# 07_Ethernet_Interface.net
KiCad netlist of a schematic drawn in Altium Designer
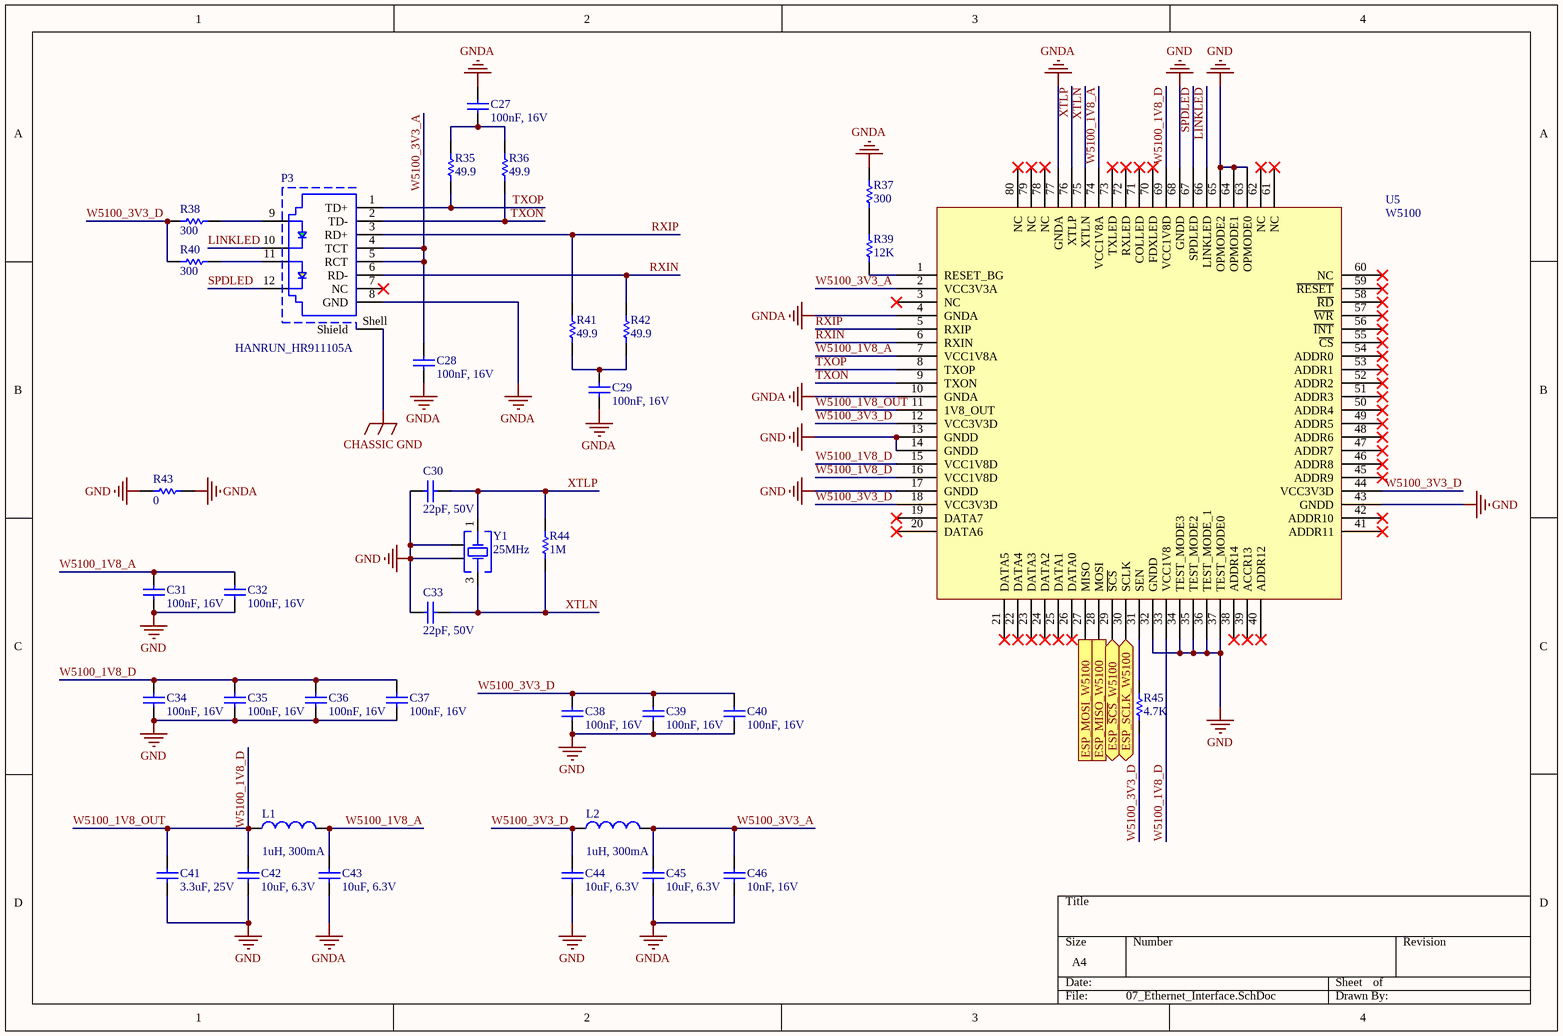
[diagram p0: 07_Ethernet_Interface.SchDoc]

(export (version "E")
  (design (tool "Eeschema 10.0.6"))
  (components
    (comp (ref "C27")
      (value "100nF, 16V")
      (footprint "WCAP-CSGP_0603_H=0.8mm_Reflow")
      (description "WCAP-CSGP Multilayer Ceramic Chip Capacitor, General Purpose, size 0603, X7R, 100nF, 16V")
      (fields
        (field (name "MANUFACTURER PART NUMBER") "885012206046")
        (field (name "MANUFACTURER") "Wurth Elektronik")
      )
      (libsource (lib "Altium_WCAP-CSGP (rev20a)") (part "885012206046"))
    )
    (comp (ref "C28")
      (value "100nF, 16V")
      (footprint "WCAP-CSGP_0603_H=0.8mm_Reflow")
      (description "WCAP-CSGP Multilayer Ceramic Chip Capacitor, General Purpose, size 0603, X7R, 100nF, 16V")
      (fields
        (field (name "MANUFACTURER PART NUMBER") "885012206046")
        (field (name "MANUFACTURER") "Wurth Elektronik")
      )
      (libsource (lib "Altium_WCAP-CSGP (rev20a)") (part "885012206046"))
    )
    (comp (ref "C29")
      (value "100nF, 16V")
      (footprint "WCAP-CSGP_0603_H=0.8mm_Reflow")
      (description "WCAP-CSGP Multilayer Ceramic Chip Capacitor, General Purpose, size 0603, X7R, 100nF, 16V")
      (fields
        (field (name "MANUFACTURER PART NUMBER") "885012206046")
        (field (name "MANUFACTURER") "Wurth Elektronik")
      )
      (libsource (lib "Altium_WCAP-CSGP (rev20a)") (part "885012206046"))
    )
    (comp (ref "C30")
      (value "22pF, 50V")
      (footprint "WCAP-CSGP_0603_H=0.8mm_Reflow")
      (description "WCAP-CSGP Multilayer Ceramic Chip Capacitor, General Purpose, size 0603, NP0, 22pF, 50V")
      (fields
        (field (name "MANUFACTURER PART NUMBER") "885012006053")
        (field (name "MANUFACTURER") "Wurth Elektronik")
      )
      (libsource (lib "Altium_WCAP-CSGP (rev20a)") (part "885012006053"))
    )
    (comp (ref "C31")
      (value "100nF, 16V")
      (footprint "WCAP-CSGP_0603_H=0.8mm_Reflow")
      (description "WCAP-CSGP Multilayer Ceramic Chip Capacitor, General Purpose, size 0603, X7R, 100nF, 16V")
      (fields
        (field (name "MANUFACTURER PART NUMBER") "885012206046")
        (field (name "MANUFACTURER") "Wurth Elektronik")
      )
      (libsource (lib "Altium_WCAP-CSGP (rev20a)") (part "885012206046"))
    )
    (comp (ref "C32")
      (value "100nF, 16V")
      (footprint "WCAP-CSGP_0603_H=0.8mm_Reflow")
      (description "WCAP-CSGP Multilayer Ceramic Chip Capacitor, General Purpose, size 0603, X7R, 100nF, 16V")
      (fields
        (field (name "MANUFACTURER PART NUMBER") "885012206046")
        (field (name "MANUFACTURER") "Wurth Elektronik")
      )
      (libsource (lib "Altium_WCAP-CSGP (rev20a)") (part "885012206046"))
    )
    (comp (ref "C33")
      (value "22pF, 50V")
      (footprint "WCAP-CSGP_0603_H=0.8mm_Reflow")
      (description "WCAP-CSGP Multilayer Ceramic Chip Capacitor, General Purpose, size 0603, NP0, 22pF, 50V")
      (fields
        (field (name "MANUFACTURER PART NUMBER") "885012006053")
        (field (name "MANUFACTURER") "Wurth Elektronik")
      )
      (libsource (lib "Altium_WCAP-CSGP (rev20a)") (part "885012006053"))
    )
    (comp (ref "C34")
      (value "100nF, 16V")
      (footprint "WCAP-CSGP_0603_H=0.8mm_Reflow")
      (description "WCAP-CSGP Multilayer Ceramic Chip Capacitor, General Purpose, size 0603, X7R, 100nF, 16V")
      (fields
        (field (name "MANUFACTURER PART NUMBER") "885012206046")
        (field (name "MANUFACTURER") "Wurth Elektronik")
      )
      (libsource (lib "Altium_WCAP-CSGP (rev20a)") (part "885012206046"))
    )
    (comp (ref "C35")
      (value "100nF, 16V")
      (footprint "WCAP-CSGP_0603_H=0.8mm_Reflow")
      (description "WCAP-CSGP Multilayer Ceramic Chip Capacitor, General Purpose, size 0603, X7R, 100nF, 16V")
      (fields
        (field (name "MANUFACTURER PART NUMBER") "885012206046")
        (field (name "MANUFACTURER") "Wurth Elektronik")
      )
      (libsource (lib "Altium_WCAP-CSGP (rev20a)") (part "885012206046"))
    )
    (comp (ref "C36")
      (value "100nF, 16V")
      (footprint "WCAP-CSGP_0603_H=0.8mm_Reflow")
      (description "WCAP-CSGP Multilayer Ceramic Chip Capacitor, General Purpose, size 0603, X7R, 100nF, 16V")
      (fields
        (field (name "MANUFACTURER PART NUMBER") "885012206046")
        (field (name "MANUFACTURER") "Wurth Elektronik")
      )
      (libsource (lib "Altium_WCAP-CSGP (rev20a)") (part "885012206046"))
    )
    (comp (ref "C37")
      (value "100nF, 16V")
      (footprint "WCAP-CSGP_0603_H=0.8mm_Reflow")
      (description "WCAP-CSGP Multilayer Ceramic Chip Capacitor, General Purpose, size 0603, X7R, 100nF, 16V")
      (fields
        (field (name "MANUFACTURER PART NUMBER") "885012206046")
        (field (name "MANUFACTURER") "Wurth Elektronik")
      )
      (libsource (lib "Altium_WCAP-CSGP (rev20a)") (part "885012206046"))
    )
    (comp (ref "C38")
      (value "100nF, 16V")
      (footprint "WCAP-CSGP_0603_H=0.8mm_Reflow")
      (description "WCAP-CSGP Multilayer Ceramic Chip Capacitor, General Purpose, size 0603, X7R, 100nF, 16V")
      (fields
        (field (name "MANUFACTURER PART NUMBER") "885012206046")
        (field (name "MANUFACTURER") "Wurth Elektronik")
      )
      (libsource (lib "Altium_WCAP-CSGP (rev20a)") (part "885012206046"))
    )
    (comp (ref "C39")
      (value "100nF, 16V")
      (footprint "WCAP-CSGP_0603_H=0.8mm_Reflow")
      (description "WCAP-CSGP Multilayer Ceramic Chip Capacitor, General Purpose, size 0603, X7R, 100nF, 16V")
      (fields
        (field (name "MANUFACTURER PART NUMBER") "885012206046")
        (field (name "MANUFACTURER") "Wurth Elektronik")
      )
      (libsource (lib "Altium_WCAP-CSGP (rev20a)") (part "885012206046"))
    )
    (comp (ref "C40")
      (value "100nF, 16V")
      (footprint "WCAP-CSGP_0603_H=0.8mm_Reflow")
      (description "WCAP-CSGP Multilayer Ceramic Chip Capacitor, General Purpose, size 0603, X7R, 100nF, 16V")
      (fields
        (field (name "MANUFACTURER PART NUMBER") "885012206046")
        (field (name "MANUFACTURER") "Wurth Elektronik")
      )
      (libsource (lib "Altium_WCAP-CSGP (rev20a)") (part "885012206046"))
    )
    (comp (ref "C41")
      (value "3.3uF, 25V")
      (footprint "WCAP-CSGP_0805_H=1.25mm")
      (description "WCAP-CSGP Multilayer Ceramic Chip Capacitor, General Purpose, size 0805, X5R, 3.3uF, 25V")
      (fields
        (field (name "MANUFACTURER PART NUMBER") "885012107017")
        (field (name "MANUFACTURER") "Wurth Elektronik")
      )
      (libsource (lib "Altium_WCAP-CSGP (rev20a)") (part "885012107017"))
    )
    (comp (ref "C42")
      (value "10uF, 6.3V")
      (footprint "WCAP-CSGP_0603_H=0.8mm_Reflow")
      (description "WCAP-CSGP Multilayer Ceramic Chip Capacitor, General Purpose, size 0603, X5R, 10uF, 6.3V")
      (fields
        (field (name "MANUFACTURER PART NUMBER") "885012106006")
        (field (name "MANUFACTURER") "Wurth Elektronik")
      )
      (libsource (lib "Altium_WCAP-CSGP (rev20a)") (part "885012106006"))
    )
    (comp (ref "C43")
      (value "10uF, 6.3V")
      (footprint "WCAP-CSGP_0603_H=0.8mm_Reflow")
      (description "WCAP-CSGP Multilayer Ceramic Chip Capacitor, General Purpose, size 0603, X5R, 10uF, 6.3V")
      (fields
        (field (name "MANUFACTURER PART NUMBER") "885012106006")
        (field (name "MANUFACTURER") "Wurth Elektronik")
      )
      (libsource (lib "Altium_WCAP-CSGP (rev20a)") (part "885012106006"))
    )
    (comp (ref "C44")
      (value "10uF, 6.3V")
      (footprint "WCAP-CSGP_0603_H=0.8mm_Reflow")
      (description "WCAP-CSGP Multilayer Ceramic Chip Capacitor, General Purpose, size 0603, X5R, 10uF, 6.3V")
      (fields
        (field (name "MANUFACTURER PART NUMBER") "885012106006")
        (field (name "MANUFACTURER") "Wurth Elektronik")
      )
      (libsource (lib "Altium_WCAP-CSGP (rev20a)") (part "885012106006"))
    )
    (comp (ref "C45")
      (value "10uF, 6.3V")
      (footprint "WCAP-CSGP_0603_H=0.8mm_Reflow")
      (description "WCAP-CSGP Multilayer Ceramic Chip Capacitor, General Purpose, size 0603, X5R, 10uF, 6.3V")
      (fields
        (field (name "MANUFACTURER PART NUMBER") "885012106006")
        (field (name "MANUFACTURER") "Wurth Elektronik")
      )
      (libsource (lib "Altium_WCAP-CSGP (rev20a)") (part "885012106006"))
    )
    (comp (ref "C46")
      (value "10nF, 16V")
      (footprint "WCAP-CSGP_0603_H=0.8mm_Reflow")
      (description "WCAP-CSGP Multilayer Ceramic Chip Capacitor, General Purpose, size 0603, X7R, 10nF, 16V")
      (fields
        (field (name "MANUFACTURER PART NUMBER") "885012206040")
        (field (name "MANUFACTURER") "Wurth Elektronik")
      )
      (libsource (lib "Altium_WCAP-CSGP (rev20a)") (part "885012206040"))
    )
    (comp (ref "L1")
      (value "1uH, 300mA")
      (footprint "I0603")
      (fields (field (name "Comment") "Inductor"))
      (libsource (lib "MiclsLib") (part "Inductor"))
    )
    (comp (ref "L2")
      (value "1uH, 300mA")
      (footprint "I0603")
      (fields (field (name "Comment") "Inductor"))
      (libsource (lib "MiclsLib") (part "Inductor"))
    )
    (comp (ref "P3")
      (value "HANRUN_HR911105A")
      (footprint "HANRUN_HR911105A")
      (libsource (lib "MiclsLib") (part "HANRUN_HR911105A"))
    )
    (comp (ref "R35")
      (value "49.9")
      (footprint "R0603")
      (fields (field (name "Comment") "Resistor"))
      (libsource (lib "MiclsLib") (part "Resistor"))
    )
    (comp (ref "R36")
      (value "49.9")
      (footprint "R0603")
      (fields (field (name "Comment") "Resistor"))
      (libsource (lib "MiclsLib") (part "Resistor"))
    )
    (comp (ref "R37")
      (value "300")
      (footprint "R0603")
      (fields (field (name "Comment") "Resistor"))
      (libsource (lib "MiclsLib") (part "Resistor"))
    )
    (comp (ref "R38")
      (value "300")
      (footprint "R0603")
      (fields (field (name "Comment") "Resistor"))
      (libsource (lib "MiclsLib") (part "Resistor"))
    )
    (comp (ref "R39")
      (value "12K")
      (footprint "R0603")
      (fields (field (name "Comment") "Resistor"))
      (libsource (lib "MiclsLib") (part "Resistor"))
    )
    (comp (ref "R40")
      (value "300")
      (footprint "R0603")
      (fields (field (name "Comment") "Resistor"))
      (libsource (lib "MiclsLib") (part "Resistor"))
    )
    (comp (ref "R41")
      (value "49.9")
      (footprint "R0603")
      (fields (field (name "Comment") "Resistor"))
      (libsource (lib "MiclsLib") (part "Resistor"))
    )
    (comp (ref "R42")
      (value "49.9")
      (footprint "R0603")
      (fields (field (name "Comment") "Resistor"))
      (libsource (lib "MiclsLib") (part "Resistor"))
    )
    (comp (ref "R43")
      (value "0")
      (footprint "R0603")
      (fields (field (name "Comment") "Resistor"))
      (libsource (lib "MiclsLib") (part "Resistor"))
    )
    (comp (ref "R44")
      (value "1M")
      (footprint "R0603")
      (fields (field (name "Comment") "Resistor"))
      (libsource (lib "MiclsLib") (part "Resistor"))
    )
    (comp (ref "R45")
      (value "4.7K")
      (footprint "R0603")
      (fields (field (name "Comment") "Resistor"))
      (libsource (lib "MiclsLib") (part "Resistor"))
    )
    (comp (ref "U5")
      (value "W5100")
      (footprint "CQFP40P1200X1200X160-80N")
      (libsource (lib "MiclsLib") (part "W5100"))
    )
    (comp (ref "Y1")
      (value "25MHz")
      (footprint "WE-XTAL_CFPX-180")
      (description "WE-XTAL Quartz Crystal, SMT, CFPX-180, 25MHz, +/-20ppm")
      (fields
        (field (name "MANUFACTURER PART NUMBER") "830108340809")
        (field (name "MANUFACTURER") "Wurth Elektronik")
      )
      (libsource (lib "Altium_WE-XTAL (rev20c)") (part "830108340809"))
    )
  )
  (nets
    (net (code "1") (name "/ESP_MISO_W5100") (class "Default")
      (node (ref "U5") (pin "28") (pinfunction "MOSI_28") (pintype "passive"))
    )
    (net (code "2") (name "/ESP_MOSI_W5100") (class "Default")
      (node (ref "U5") (pin "27") (pinfunction "MISO_27") (pintype "passive"))
    )
    (net (code "3") (name "/ESP_SCLK_W5100") (class "Default")
      (node (ref "U5") (pin "30") (pinfunction "SCLK_30") (pintype "passive"))
    )
    (net (code "4") (name "/ESP_~{SCS}_W5100") (class "Default")
      (node (ref "U5") (pin "29") (pinfunction "~{SCS}_29") (pintype "passive"))
    )
    (net (code "5") (name "/LINKLED") (class "Default")
      (node (ref "P3") (pin "10") (pinfunction "10_10") (pintype "passive"))
      (node (ref "U5") (pin "66") (pinfunction "LINKLED_66") (pintype "passive"))
    )
    (net (code "6") (name "/RXIN") (class "Default")
      (node (ref "P3") (pin "6") (pinfunction "RD-_6") (pintype "passive"))
      (node (ref "R42") (pin "1") (pinfunction "1_1") (pintype "passive"))
      (node (ref "U5") (pin "6") (pinfunction "RXIN_6") (pintype "passive"))
    )
    (net (code "7") (name "/RXIP") (class "Default")
      (node (ref "P3") (pin "3") (pinfunction "RD+_3") (pintype "passive"))
      (node (ref "R41") (pin "1") (pinfunction "1_1") (pintype "passive"))
      (node (ref "U5") (pin "5") (pinfunction "RXIP_5") (pintype "passive"))
    )
    (net (code "8") (name "/SPDLED") (class "Default")
      (node (ref "P3") (pin "12") (pinfunction "12_12") (pintype "passive"))
      (node (ref "U5") (pin "67") (pinfunction "SPDLED_67") (pintype "passive"))
    )
    (net (code "9") (name "/TXON") (class "Default")
      (node (ref "P3") (pin "2") (pinfunction "TD-_2") (pintype "passive"))
      (node (ref "R36") (pin "1") (pinfunction "1_1") (pintype "passive"))
      (node (ref "U5") (pin "9") (pinfunction "TXON_9") (pintype "passive"))
    )
    (net (code "10") (name "/TXOP") (class "Default")
      (node (ref "P3") (pin "1") (pinfunction "TD+_1") (pintype "passive"))
      (node (ref "R35") (pin "1") (pinfunction "1_1") (pintype "passive"))
      (node (ref "U5") (pin "8") (pinfunction "TXOP_8") (pintype "passive"))
    )
    (net (code "11") (name "/W5100_1V8_A") (class "Default")
      (node (ref "C31") (pin "2") (pinfunction "2_2") (pintype "passive"))
      (node (ref "C32") (pin "2") (pinfunction "2_2") (pintype "passive"))
      (node (ref "C43") (pin "2") (pinfunction "2_2") (pintype "passive"))
      (node (ref "L1") (pin "2") (pinfunction "2_2") (pintype "passive"))
      (node (ref "U5") (pin "7") (pinfunction "VCC1V8A_7") (pintype "passive"))
      (node (ref "U5") (pin "74") (pinfunction "VCC1V8A_74") (pintype "passive"))
    )
    (net (code "12") (name "/W5100_1V8_D") (class "Default")
      (node (ref "C34") (pin "2") (pinfunction "2_2") (pintype "passive"))
      (node (ref "C35") (pin "2") (pinfunction "2_2") (pintype "passive"))
      (node (ref "C36") (pin "2") (pinfunction "2_2") (pintype "passive"))
      (node (ref "C37") (pin "2") (pinfunction "2_2") (pintype "passive"))
      (node (ref "C41") (pin "2") (pinfunction "2_2") (pintype "passive"))
      (node (ref "C42") (pin "2") (pinfunction "2_2") (pintype "passive"))
      (node (ref "L1") (pin "1") (pinfunction "1_1") (pintype "passive"))
      (node (ref "U5") (pin "11") (pinfunction "1V8_OUT_11") (pintype "passive"))
      (node (ref "U5") (pin "15") (pinfunction "VCC1V8D_15") (pintype "passive"))
      (node (ref "U5") (pin "16") (pinfunction "VCC1V8D_16") (pintype "passive"))
      (node (ref "U5") (pin "33") (pinfunction "VCC1V8_33") (pintype "passive"))
      (node (ref "U5") (pin "69") (pinfunction "VCC1V8D_69") (pintype "passive"))
    )
    (net (code "13") (name "/W5100_3V3_A") (class "Default")
      (node (ref "C28") (pin "2") (pinfunction "2_2") (pintype "passive"))
      (node (ref "C45") (pin "2") (pinfunction "2_2") (pintype "passive"))
      (node (ref "C46") (pin "2") (pinfunction "2_2") (pintype "passive"))
      (node (ref "L2") (pin "2") (pinfunction "2_2") (pintype "passive"))
      (node (ref "P3") (pin "4") (pinfunction "TCT_4") (pintype "passive"))
      (node (ref "P3") (pin "5") (pinfunction "RCT_5") (pintype "passive"))
      (node (ref "U5") (pin "2") (pinfunction "VCC3V3A_2") (pintype "passive"))
    )
    (net (code "14") (name "/W5100_3V3_D") (class "Default")
      (node (ref "C38") (pin "2") (pinfunction "2_2") (pintype "passive"))
      (node (ref "C39") (pin "2") (pinfunction "2_2") (pintype "passive"))
      (node (ref "C40") (pin "2") (pinfunction "2_2") (pintype "passive"))
      (node (ref "C44") (pin "2") (pinfunction "2_2") (pintype "passive"))
      (node (ref "L2") (pin "1") (pinfunction "1_1") (pintype "passive"))
      (node (ref "R38") (pin "2") (pinfunction "2_2") (pintype "passive"))
      (node (ref "R40") (pin "2") (pinfunction "2_2") (pintype "passive"))
      (node (ref "R45") (pin "1") (pinfunction "1_1") (pintype "passive"))
      (node (ref "U5") (pin "12") (pinfunction "VCC3V3D_12") (pintype "passive"))
      (node (ref "U5") (pin "18") (pinfunction "VCC3V3D_18") (pintype "passive"))
      (node (ref "U5") (pin "44") (pinfunction "VCC3V3D_44") (pintype "passive"))
    )
    (net (code "15") (name "/XTLN") (class "Default")
      (node (ref "C33") (pin "2") (pinfunction "2_2") (pintype "passive"))
      (node (ref "R44") (pin "1") (pinfunction "1_1") (pintype "passive"))
      (node (ref "U5") (pin "75") (pinfunction "XTLN_75") (pintype "passive"))
      (node (ref "Y1") (pin "3") (pinfunction "Crystal_3") (pintype "passive"))
    )
    (net (code "16") (name "/XTLP") (class "Default")
      (node (ref "C30") (pin "2") (pinfunction "2_2") (pintype "passive"))
      (node (ref "R44") (pin "2") (pinfunction "2_2") (pintype "passive"))
      (node (ref "U5") (pin "76") (pinfunction "XTLP_76") (pintype "passive"))
      (node (ref "Y1") (pin "1") (pinfunction "Crystal_1") (pintype "passive"))
    )
    (net (code "17") (name "CHASSIC GND") (class "Default")
      (node (ref "P3") (pin "Shell") (pinfunction "Shield_Shell") (pintype "passive"))
    )
    (net (code "18") (name "GND") (class "Default")
      (node (ref "C30") (pin "1") (pinfunction "1_1") (pintype "passive"))
      (node (ref "C31") (pin "1") (pinfunction "1_1") (pintype "passive"))
      (node (ref "C32") (pin "1") (pinfunction "1_1") (pintype "passive"))
      (node (ref "C33") (pin "1") (pinfunction "1_1") (pintype "passive"))
      (node (ref "C34") (pin "1") (pinfunction "1_1") (pintype "passive"))
      (node (ref "C35") (pin "1") (pinfunction "1_1") (pintype "passive"))
      (node (ref "C36") (pin "1") (pinfunction "1_1") (pintype "passive"))
      (node (ref "C37") (pin "1") (pinfunction "1_1") (pintype "passive"))
      (node (ref "C38") (pin "1") (pinfunction "1_1") (pintype "passive"))
      (node (ref "C39") (pin "1") (pinfunction "1_1") (pintype "passive"))
      (node (ref "C40") (pin "1") (pinfunction "1_1") (pintype "passive"))
      (node (ref "C41") (pin "1") (pinfunction "1_1") (pintype "passive"))
      (node (ref "C42") (pin "1") (pinfunction "1_1") (pintype "passive"))
      (node (ref "C44") (pin "1") (pinfunction "1_1") (pintype "passive"))
      (node (ref "R43") (pin "2") (pinfunction "2_2") (pintype "passive"))
      (node (ref "U5") (pin "13") (pinfunction "GNDD_13") (pintype "passive"))
      (node (ref "U5") (pin "14") (pinfunction "GNDD_14") (pintype "passive"))
      (node (ref "U5") (pin "17") (pinfunction "GNDD_17") (pintype "passive"))
      (node (ref "U5") (pin "32") (pinfunction "GNDD_32") (pintype "passive"))
      (node (ref "U5") (pin "34") (pinfunction "TEST_MODE3_34") (pintype "passive"))
      (node (ref "U5") (pin "35") (pinfunction "TEST_MODE2_35") (pintype "passive"))
      (node (ref "U5") (pin "36") (pinfunction "TEST_MODE_1_36") (pintype "passive"))
      (node (ref "U5") (pin "37") (pinfunction "TEST_MODE0_37") (pintype "passive"))
      (node (ref "U5") (pin "43") (pinfunction "GNDD_43") (pintype "passive"))
      (node (ref "U5") (pin "63") (pinfunction "OPMODE0_63") (pintype "passive"))
      (node (ref "U5") (pin "64") (pinfunction "OPMODE1_64") (pintype "passive"))
      (node (ref "U5") (pin "65") (pinfunction "OPMODE2_65") (pintype "passive"))
      (node (ref "U5") (pin "68") (pinfunction "GNDD_68") (pintype "passive"))
      (node (ref "Y1") (pin "2") (pinfunction "GND&Lid_2") (pintype "passive"))
      (node (ref "Y1") (pin "4") (pinfunction "GND&Lid_4") (pintype "passive"))
    )
    (net (code "19") (name "GNDA") (class "Default")
      (node (ref "C27") (pin "2") (pinfunction "2_2") (pintype "passive"))
      (node (ref "C28") (pin "1") (pinfunction "1_1") (pintype "passive"))
      (node (ref "C29") (pin "2") (pinfunction "2_2") (pintype "passive"))
      (node (ref "C43") (pin "1") (pinfunction "1_1") (pintype "passive"))
      (node (ref "C45") (pin "1") (pinfunction "1_1") (pintype "passive"))
      (node (ref "C46") (pin "1") (pinfunction "1_1") (pintype "passive"))
      (node (ref "P3") (pin "8") (pinfunction "GND_8") (pintype "passive"))
      (node (ref "R37") (pin "2") (pinfunction "2_2") (pintype "passive"))
      (node (ref "R43") (pin "1") (pinfunction "1_1") (pintype "passive"))
      (node (ref "U5") (pin "10") (pinfunction "GNDA_10") (pintype "passive"))
      (node (ref "U5") (pin "4") (pinfunction "GNDA_4") (pintype "passive"))
      (node (ref "U5") (pin "77") (pinfunction "GNDA_77") (pintype "passive"))
    )
    (net (code "20") (name "Net-(C27-Pad1)") (class "Default")
      (node (ref "C27") (pin "1") (pinfunction "1_1") (pintype "passive"))
      (node (ref "R35") (pin "2") (pinfunction "2_2") (pintype "passive"))
      (node (ref "R36") (pin "2") (pinfunction "2_2") (pintype "passive"))
    )
    (net (code "21") (name "Net-(C29-Pad1)") (class "Default")
      (node (ref "C29") (pin "1") (pinfunction "1_1") (pintype "passive"))
      (node (ref "R41") (pin "2") (pinfunction "2_2") (pintype "passive"))
      (node (ref "R42") (pin "2") (pinfunction "2_2") (pintype "passive"))
    )
    (net (code "22") (name "Net-(P3-Pad9)") (class "Default")
      (node (ref "P3") (pin "9") (pinfunction "9_9") (pintype "passive"))
      (node (ref "R38") (pin "1") (pinfunction "1_1") (pintype "passive"))
    )
    (net (code "23") (name "Net-(P3-Pad11)") (class "Default")
      (node (ref "P3") (pin "11") (pinfunction "11_11") (pintype "passive"))
      (node (ref "R40") (pin "1") (pinfunction "1_1") (pintype "passive"))
    )
    (net (code "24") (name "Net-(R37-Pad1)") (class "Default")
      (node (ref "R37") (pin "1") (pinfunction "1_1") (pintype "passive"))
      (node (ref "R39") (pin "2") (pinfunction "2_2") (pintype "passive"))
    )
    (net (code "25") (name "Net-(U5-RESET_BG)") (class "Default")
      (node (ref "R39") (pin "1") (pinfunction "1_1") (pintype "passive"))
      (node (ref "U5") (pin "1") (pinfunction "RESET_BG_1") (pintype "passive"))
    )
    (net (code "26") (name "Net-(U5-SEN)") (class "Default")
      (node (ref "R45") (pin "2") (pinfunction "2_2") (pintype "passive"))
      (node (ref "U5") (pin "31") (pinfunction "SEN_31") (pintype "passive"))
    )
    (net (code "27") (name "unconnected-(P3-NC-Pad7)") (class "Default")
      (node (ref "P3") (pin "7") (pinfunction "NC_7") (pintype "passive+no_connect"))
    )
    (net (code "28") (name "unconnected-(U5-ACCR13-Pad39)") (class "Default")
      (node (ref "U5") (pin "39") (pinfunction "ACCR13_39") (pintype "passive+no_connect"))
    )
    (net (code "29") (name "unconnected-(U5-ADDR0-Pad54)") (class "Default")
      (node (ref "U5") (pin "54") (pinfunction "ADDR0_54") (pintype "passive+no_connect"))
    )
    (net (code "30") (name "unconnected-(U5-ADDR1-Pad53)") (class "Default")
      (node (ref "U5") (pin "53") (pinfunction "ADDR1_53") (pintype "passive+no_connect"))
    )
    (net (code "31") (name "unconnected-(U5-ADDR2-Pad52)") (class "Default")
      (node (ref "U5") (pin "52") (pinfunction "ADDR2_52") (pintype "passive+no_connect"))
    )
    (net (code "32") (name "unconnected-(U5-ADDR3-Pad51)") (class "Default")
      (node (ref "U5") (pin "51") (pinfunction "ADDR3_51") (pintype "passive+no_connect"))
    )
    (net (code "33") (name "unconnected-(U5-ADDR4-Pad50)") (class "Default")
      (node (ref "U5") (pin "50") (pinfunction "ADDR4_50") (pintype "passive+no_connect"))
    )
    (net (code "34") (name "unconnected-(U5-ADDR5-Pad49)") (class "Default")
      (node (ref "U5") (pin "49") (pinfunction "ADDR5_49") (pintype "passive+no_connect"))
    )
    (net (code "35") (name "unconnected-(U5-ADDR6-Pad48)") (class "Default")
      (node (ref "U5") (pin "48") (pinfunction "ADDR6_48") (pintype "passive+no_connect"))
    )
    (net (code "36") (name "unconnected-(U5-ADDR7-Pad47)") (class "Default")
      (node (ref "U5") (pin "47") (pinfunction "ADDR7_47") (pintype "passive+no_connect"))
    )
    (net (code "37") (name "unconnected-(U5-ADDR8-Pad46)") (class "Default")
      (node (ref "U5") (pin "46") (pinfunction "ADDR8_46") (pintype "passive+no_connect"))
    )
    (net (code "38") (name "unconnected-(U5-ADDR9-Pad45)") (class "Default")
      (node (ref "U5") (pin "45") (pinfunction "ADDR9_45") (pintype "passive+no_connect"))
    )
    (net (code "39") (name "unconnected-(U5-ADDR10-Pad42)") (class "Default")
      (node (ref "U5") (pin "42") (pinfunction "ADDR10_42") (pintype "passive+no_connect"))
    )
    (net (code "40") (name "unconnected-(U5-ADDR11-Pad41)") (class "Default")
      (node (ref "U5") (pin "41") (pinfunction "ADDR11_41") (pintype "passive+no_connect"))
    )
    (net (code "41") (name "unconnected-(U5-ADDR12-Pad40)") (class "Default")
      (node (ref "U5") (pin "40") (pinfunction "ADDR12_40") (pintype "passive+no_connect"))
    )
    (net (code "42") (name "unconnected-(U5-ADDR14-Pad38)") (class "Default")
      (node (ref "U5") (pin "38") (pinfunction "ADDR14_38") (pintype "passive+no_connect"))
    )
    (net (code "43") (name "unconnected-(U5-COLLED-Pad71)") (class "Default")
      (node (ref "U5") (pin "71") (pinfunction "COLLED_71") (pintype "passive+no_connect"))
    )
    (net (code "44") (name "unconnected-(U5-DATA0-Pad26)") (class "Default")
      (node (ref "U5") (pin "26") (pinfunction "DATA0_26") (pintype "passive+no_connect"))
    )
    (net (code "45") (name "unconnected-(U5-DATA1-Pad25)") (class "Default")
      (node (ref "U5") (pin "25") (pinfunction "DATA1_25") (pintype "passive+no_connect"))
    )
    (net (code "46") (name "unconnected-(U5-DATA2-Pad24)") (class "Default")
      (node (ref "U5") (pin "24") (pinfunction "DATA2_24") (pintype "passive+no_connect"))
    )
    (net (code "47") (name "unconnected-(U5-DATA3-Pad23)") (class "Default")
      (node (ref "U5") (pin "23") (pinfunction "DATA3_23") (pintype "passive+no_connect"))
    )
    (net (code "48") (name "unconnected-(U5-DATA4-Pad22)") (class "Default")
      (node (ref "U5") (pin "22") (pinfunction "DATA4_22") (pintype "passive+no_connect"))
    )
    (net (code "49") (name "unconnected-(U5-DATA5-Pad21)") (class "Default")
      (node (ref "U5") (pin "21") (pinfunction "DATA5_21") (pintype "passive+no_connect"))
    )
    (net (code "50") (name "unconnected-(U5-DATA6-Pad20)") (class "Default")
      (node (ref "U5") (pin "20") (pinfunction "DATA6_20") (pintype "passive+no_connect"))
    )
    (net (code "51") (name "unconnected-(U5-DATA7-Pad19)") (class "Default")
      (node (ref "U5") (pin "19") (pinfunction "DATA7_19") (pintype "passive+no_connect"))
    )
    (net (code "52") (name "unconnected-(U5-FDXLED-Pad70)") (class "Default")
      (node (ref "U5") (pin "70") (pinfunction "FDXLED_70") (pintype "passive+no_connect"))
    )
    (net (code "53") (name "unconnected-(U5-NC-Pad3)") (class "Default")
      (node (ref "U5") (pin "3") (pinfunction "NC_3") (pintype "passive+no_connect"))
    )
    (net (code "54") (name "unconnected-(U5-NC-Pad60)") (class "Default")
      (node (ref "U5") (pin "60") (pinfunction "NC_60") (pintype "passive+no_connect"))
    )
    (net (code "55") (name "unconnected-(U5-NC-Pad61)") (class "Default")
      (node (ref "U5") (pin "61") (pinfunction "NC_61") (pintype "passive+no_connect"))
    )
    (net (code "56") (name "unconnected-(U5-NC-Pad62)") (class "Default")
      (node (ref "U5") (pin "62") (pinfunction "NC_62") (pintype "passive+no_connect"))
    )
    (net (code "57") (name "unconnected-(U5-NC-Pad78)") (class "Default")
      (node (ref "U5") (pin "78") (pinfunction "NC_78") (pintype "passive+no_connect"))
    )
    (net (code "58") (name "unconnected-(U5-NC-Pad79)") (class "Default")
      (node (ref "U5") (pin "79") (pinfunction "NC_79") (pintype "passive+no_connect"))
    )
    (net (code "59") (name "unconnected-(U5-NC-Pad80)") (class "Default")
      (node (ref "U5") (pin "80") (pinfunction "NC_80") (pintype "passive+no_connect"))
    )
    (net (code "60") (name "unconnected-(U5-RXLED-Pad72)") (class "Default")
      (node (ref "U5") (pin "72") (pinfunction "RXLED_72") (pintype "passive+no_connect"))
    )
    (net (code "61") (name "unconnected-(U5-TXLED-Pad73)") (class "Default")
      (node (ref "U5") (pin "73") (pinfunction "TXLED_73") (pintype "passive+no_connect"))
    )
    (net (code "62") (name "unconnected-(U5-~{CS}-Pad55)") (class "Default")
      (node (ref "U5") (pin "55") (pinfunction "~{CS}_55") (pintype "passive+no_connect"))
    )
    (net (code "63") (name "unconnected-(U5-~{INT}-Pad56)") (class "Default")
      (node (ref "U5") (pin "56") (pinfunction "~{INT}_56") (pintype "passive+no_connect"))
    )
    (net (code "64") (name "unconnected-(U5-~{RD}-Pad58)") (class "Default")
      (node (ref "U5") (pin "58") (pinfunction "~{RD}_58") (pintype "passive+no_connect"))
    )
    (net (code "65") (name "unconnected-(U5-~{RESET}-Pad59)") (class "Default")
      (node (ref "U5") (pin "59") (pinfunction "~{RESET}_59") (pintype "passive+no_connect"))
    )
    (net (code "66") (name "unconnected-(U5-~{WR}-Pad57)") (class "Default")
      (node (ref "U5") (pin "57") (pinfunction "~{WR}_57") (pintype "passive+no_connect"))
    )
  )
)
